# adc2018.net
KiCad netlist of a schematic drawn in EAGLE
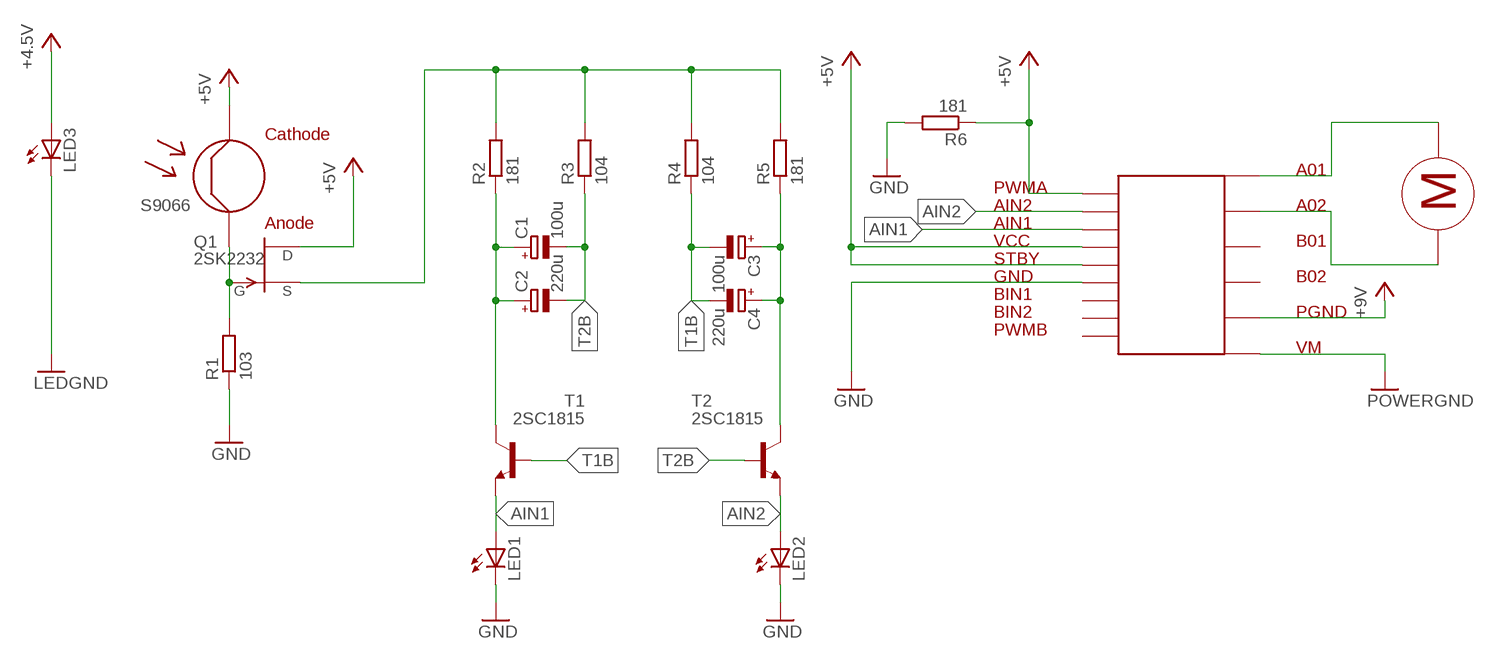
[diagram p0: schematic, sheet 1]

(export (version "E")
  (design (tool "Eeschema 10.0.6"))
  (components
    (comp (ref "C1")
      (value "100u")
      (footprint "eagle-import:E2-5")
      (libsource (lib "eagle-import") (part "CPOL-EUE2-5"))
    )
    (comp (ref "C2")
      (value "220u")
      (footprint "eagle-import:E2-5")
      (libsource (lib "eagle-import") (part "CPOL-EUE2-5"))
    )
    (comp (ref "C3")
      (value "100u")
      (footprint "eagle-import:E2-5")
      (libsource (lib "eagle-import") (part "CPOL-EUE2-5"))
    )
    (comp (ref "C4")
      (value "220u")
      (footprint "eagle-import:E2-5")
      (libsource (lib "eagle-import") (part "CPOL-EUE2-5"))
    )
    (comp (ref "D1")
      (value "S9066")
      (footprint "eagle-import:S9066")
      (libsource (lib "eagle-import") (part "S9066"))
    )
    (comp (ref "LED1")
      (value "LED5MM")
      (footprint "eagle-import:LED5MM")
      (libsource (lib "eagle-import") (part "LED5MM"))
    )
    (comp (ref "LED2")
      (value "LED5MM")
      (footprint "eagle-import:LED5MM")
      (libsource (lib "eagle-import") (part "LED5MM"))
    )
    (comp (ref "LED3")
      (value "LED5MM")
      (footprint "eagle-import:LED5MM")
      (libsource (lib "eagle-import") (part "LED5MM"))
    )
    (comp (ref "M1")
      (value "MOTOR")
      (footprint "eagle-import:MOTOR")
      (libsource (lib "eagle-import") (part "MOTOR"))
    )
    (comp (ref "MD1")
      (value "TB6612")
      (footprint "eagle-import:TB6612")
      (libsource (lib "eagle-import") (part "TB6612"))
    )
    (comp (ref "Q1")
      (value "2SK2232")
      (footprint "eagle-import:2SK241")
      (libsource (lib "eagle-import") (part "2SK2232"))
    )
    (comp (ref "R1")
      (value "103")
      (footprint "eagle-import:0617_22")
      (libsource (lib "eagle-import") (part "R-EU_0617/22"))
    )
    (comp (ref "R2")
      (value "181")
      (footprint "eagle-import:0617_22")
      (libsource (lib "eagle-import") (part "R-EU_0617/22"))
    )
    (comp (ref "R3")
      (value "104")
      (footprint "eagle-import:0617_22")
      (libsource (lib "eagle-import") (part "R-EU_0617/22"))
    )
    (comp (ref "R4")
      (value "104")
      (footprint "eagle-import:0617_22")
      (libsource (lib "eagle-import") (part "R-EU_0617/22"))
    )
    (comp (ref "R5")
      (value "181")
      (footprint "eagle-import:0617_22")
      (libsource (lib "eagle-import") (part "R-EU_0617/22"))
    )
    (comp (ref "R6")
      (value "181")
      (footprint "eagle-import:0309_12")
      (libsource (lib "eagle-import") (part "R-EU_0309/12"))
    )
    (comp (ref "T1")
      (value "2SC1815")
      (footprint "eagle-import:TO92-ECB")
      (libsource (lib "eagle-import") (part "2SC1815"))
    )
    (comp (ref "T2")
      (value "2SC1815")
      (footprint "eagle-import:TO92-ECB")
      (libsource (lib "eagle-import") (part "2SC1815"))
    )
  )
  (nets
    (net (code "1") (name "+4.5V") (class "Default")
      (node (ref "D1") (pin "P$1") (pinfunction "P$1_P$1") (pintype "bidirectional"))
      (node (ref "LED3") (pin "A") (pinfunction "A_A") (pintype "passive"))
      (node (ref "MD1") (pin "P$1") (pinfunction "P$1_P$1") (pintype "bidirectional"))
      (node (ref "MD1") (pin "P$13") (pinfunction "P$13_P$13") (pintype "bidirectional"))
      (node (ref "MD1") (pin "P$4") (pinfunction "P$4_P$4") (pintype "bidirectional"))
      (node (ref "MD1") (pin "P$5") (pinfunction "P$5_P$5") (pintype "bidirectional"))
      (node (ref "Q1") (pin "1") (pinfunction "D_1") (pintype "passive"))
      (node (ref "R6") (pin "1") (pinfunction "1_1") (pintype "passive"))
    )
    (net (code "2") (name "AIN1") (class "Default")
      (node (ref "LED1") (pin "A") (pinfunction "A_A") (pintype "passive"))
      (node (ref "MD1") (pin "P$3") (pinfunction "P$3_P$3") (pintype "bidirectional"))
      (node (ref "T1") (pin "E") (pinfunction "E_E") (pintype "passive"))
    )
    (net (code "3") (name "AIN2") (class "Default")
      (node (ref "LED2") (pin "A") (pinfunction "A_A") (pintype "passive"))
      (node (ref "MD1") (pin "P$2") (pinfunction "P$2_P$2") (pintype "bidirectional"))
      (node (ref "T2") (pin "E") (pinfunction "E_E") (pintype "passive"))
    )
    (net (code "4") (name "GND") (class "Default")
      (node (ref "LED1") (pin "K") (pinfunction "C_K") (pintype "passive"))
      (node (ref "LED2") (pin "K") (pinfunction "C_K") (pintype "passive"))
      (node (ref "LED3") (pin "K") (pinfunction "C_K") (pintype "passive"))
      (node (ref "MD1") (pin "P$15") (pinfunction "P$15_P$15") (pintype "bidirectional"))
      (node (ref "MD1") (pin "P$6") (pinfunction "P$6_P$6") (pintype "bidirectional"))
      (node (ref "R1") (pin "1") (pinfunction "1_1") (pintype "passive"))
      (node (ref "R6") (pin "2") (pinfunction "2_2") (pintype "passive"))
    )
    (net (code "5") (name "Net-(C1-Pad+)") (class "Default")
      (node (ref "C1") (pin "+") (pinfunction "+_+") (pintype "passive"))
      (node (ref "C2") (pin "+") (pinfunction "+_+") (pintype "passive"))
      (node (ref "R2") (pin "1") (pinfunction "1_1") (pintype "passive"))
      (node (ref "T1") (pin "C") (pinfunction "C_C") (pintype "passive"))
    )
    (net (code "6") (name "Net-(C3-Pad+)") (class "Default")
      (node (ref "C3") (pin "+") (pinfunction "+_+") (pintype "passive"))
      (node (ref "C4") (pin "+") (pinfunction "+_+") (pintype "passive"))
      (node (ref "R5") (pin "1") (pinfunction "1_1") (pintype "passive"))
      (node (ref "T2") (pin "C") (pinfunction "C_C") (pintype "passive"))
    )
    (net (code "7") (name "Net-(M1-PadP$1)") (class "Default")
      (node (ref "M1") (pin "P$1") (pinfunction "P$1_P$1") (pintype "bidirectional"))
      (node (ref "MD1") (pin "P$10") (pinfunction "P$10_P$10") (pintype "bidirectional"))
    )
    (net (code "8") (name "Net-(M1-PadP$2)") (class "Default")
      (node (ref "M1") (pin "P$2") (pinfunction "P$2_P$2") (pintype "bidirectional"))
      (node (ref "MD1") (pin "P$14") (pinfunction "P$14_P$14") (pintype "bidirectional"))
    )
    (net (code "9") (name "Net-(Q1-G)") (class "Default")
      (node (ref "D1") (pin "P$2") (pinfunction "P$2_P$2") (pintype "bidirectional"))
      (node (ref "Q1") (pin "2") (pinfunction "G_2") (pintype "passive"))
      (node (ref "R1") (pin "2") (pinfunction "2_2") (pintype "passive"))
    )
    (net (code "10") (name "Net-(Q1-S)") (class "Default")
      (node (ref "Q1") (pin "3") (pinfunction "S_3") (pintype "passive"))
      (node (ref "R2") (pin "2") (pinfunction "2_2") (pintype "passive"))
      (node (ref "R3") (pin "2") (pinfunction "2_2") (pintype "passive"))
      (node (ref "R4") (pin "2") (pinfunction "2_2") (pintype "passive"))
      (node (ref "R5") (pin "2") (pinfunction "2_2") (pintype "passive"))
    )
    (net (code "11") (name "T1B") (class "Default")
      (node (ref "C3") (pin "-") (pinfunction "-_-") (pintype "passive"))
      (node (ref "C4") (pin "-") (pinfunction "-_-") (pintype "passive"))
      (node (ref "R4") (pin "1") (pinfunction "1_1") (pintype "passive"))
      (node (ref "T1") (pin "B") (pinfunction "B_B") (pintype "passive"))
    )
    (net (code "12") (name "T2B") (class "Default")
      (node (ref "C1") (pin "-") (pinfunction "-_-") (pintype "passive"))
      (node (ref "C2") (pin "-") (pinfunction "-_-") (pintype "passive"))
      (node (ref "R3") (pin "1") (pinfunction "1_1") (pintype "passive"))
      (node (ref "T2") (pin "B") (pinfunction "B_B") (pintype "passive"))
    )
    (net (code "13") (name "unconnected-(MD1-PadP$7)") (class "Default")
      (node (ref "MD1") (pin "P$7") (pinfunction "P$7_P$7") (pintype "bidirectional"))
    )
    (net (code "14") (name "unconnected-(MD1-PadP$8)") (class "Default")
      (node (ref "MD1") (pin "P$8") (pinfunction "P$8_P$8") (pintype "bidirectional"))
    )
    (net (code "15") (name "unconnected-(MD1-PadP$9)") (class "Default")
      (node (ref "MD1") (pin "P$9") (pinfunction "P$9_P$9") (pintype "bidirectional"))
    )
    (net (code "16") (name "unconnected-(MD1-PadP$11)") (class "Default")
      (node (ref "MD1") (pin "P$11") (pinfunction "P$11_P$11") (pintype "bidirectional"))
    )
    (net (code "17") (name "unconnected-(MD1-PadP$12)") (class "Default")
      (node (ref "MD1") (pin "P$12") (pinfunction "P$12_P$12") (pintype "bidirectional"))
    )
  )
)
